# MCC8.net
KiCad netlist of a schematic drawn in EAGLE
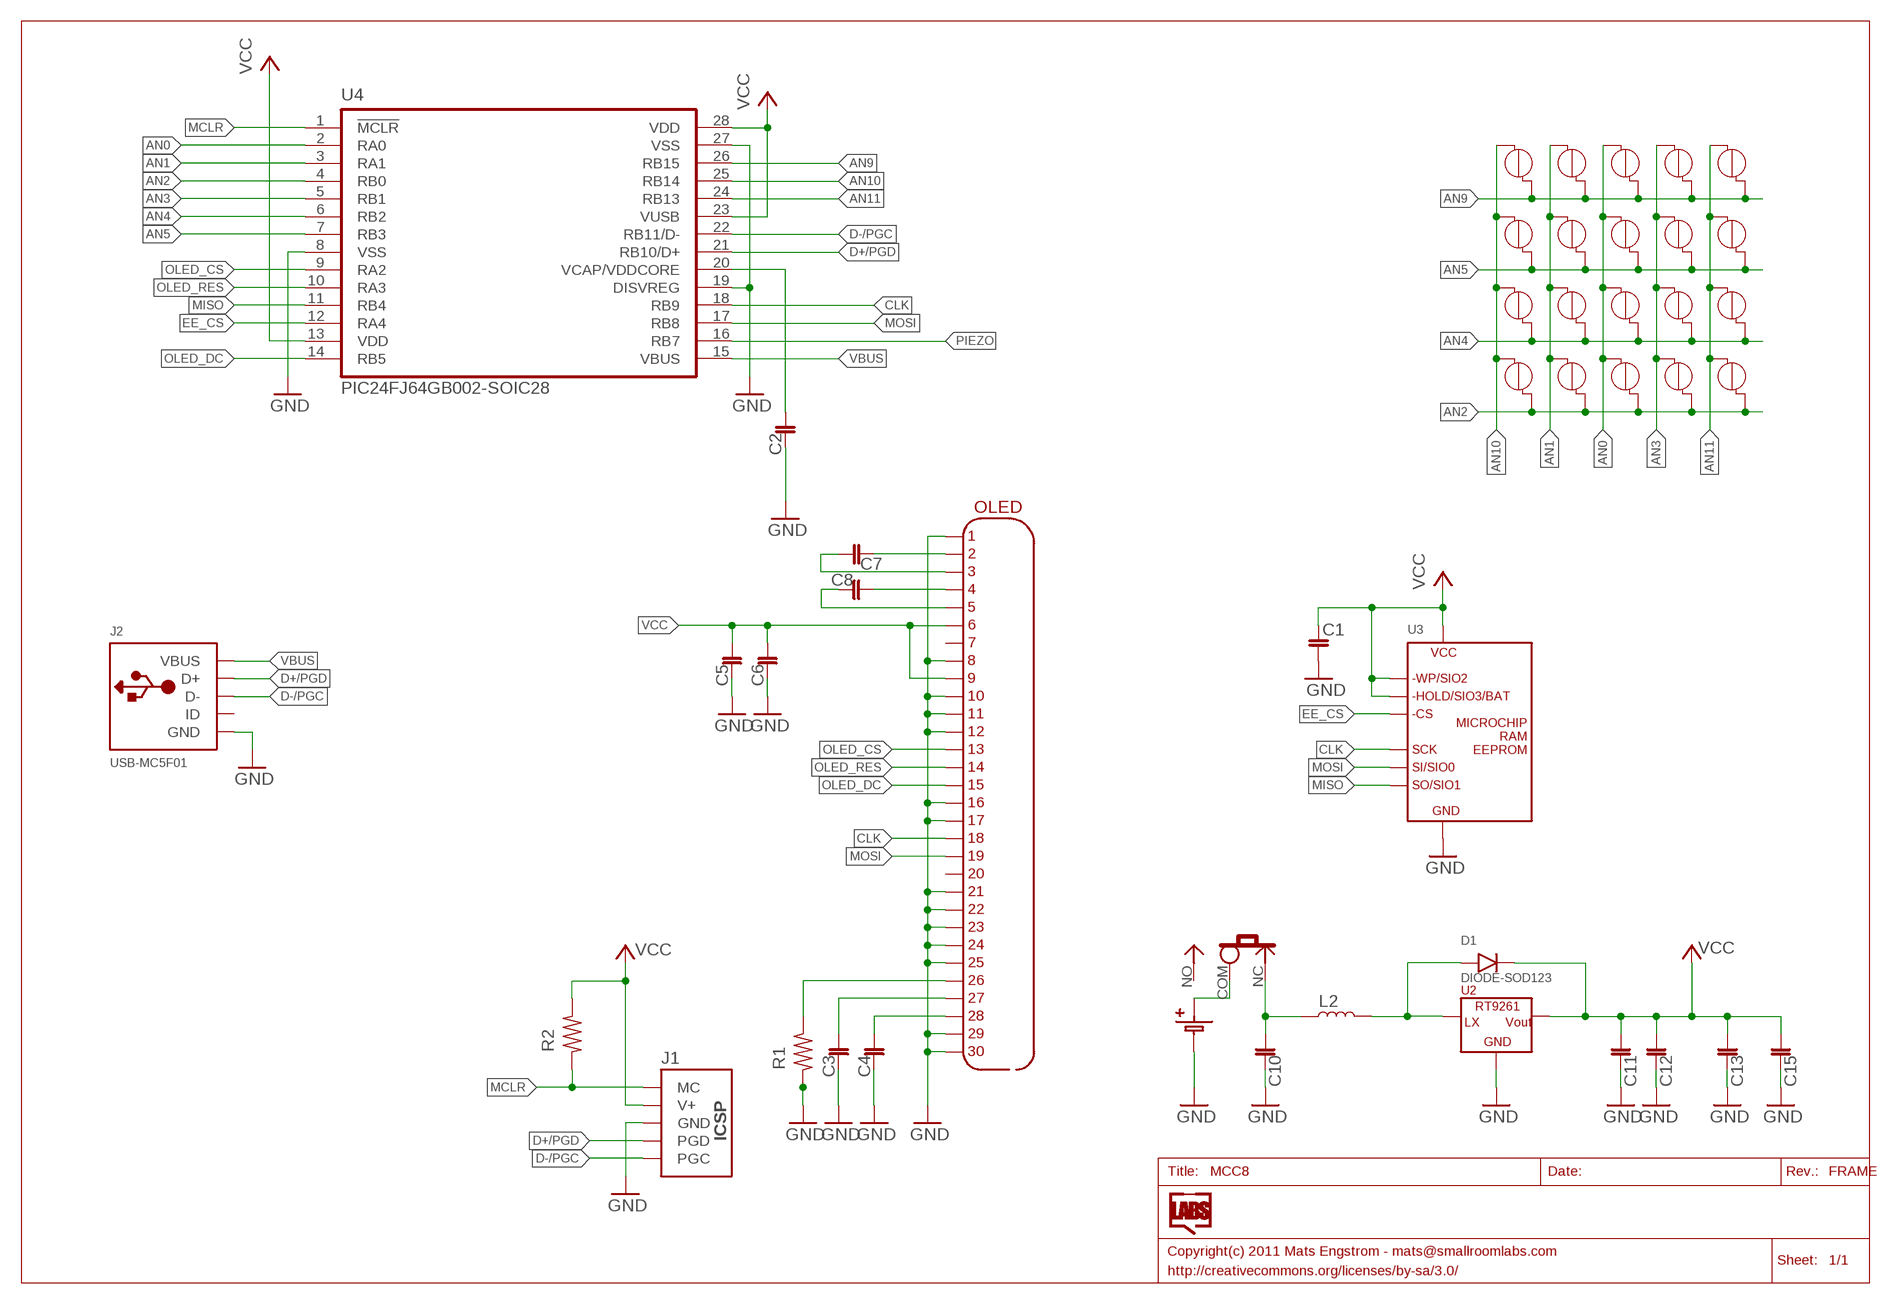
[diagram p0: schematic, sheet 1]

(export (version "E")
  (design (tool "Eeschema 10.0.6"))
  (components
    (comp (ref "B1")
      (value "TOUCH-CAP2-7")
      (footprint "eagle-import:TOUCH-CAP2-7MM")
      (libsource (lib "eagle-import") (part "TOUCH-CAP2-7"))
    )
    (comp (ref "B2")
      (value "TOUCH-CAP2-7")
      (footprint "eagle-import:TOUCH-CAP2-7MM")
      (libsource (lib "eagle-import") (part "TOUCH-CAP2-7"))
    )
    (comp (ref "B3")
      (value "TOUCH-CAP2-7")
      (footprint "eagle-import:TOUCH-CAP2-7MM")
      (libsource (lib "eagle-import") (part "TOUCH-CAP2-7"))
    )
    (comp (ref "B4")
      (value "TOUCH-CAP2-7")
      (footprint "eagle-import:TOUCH-CAP2-7MM")
      (libsource (lib "eagle-import") (part "TOUCH-CAP2-7"))
    )
    (comp (ref "B5")
      (value "TOUCH-CAP2-7")
      (footprint "eagle-import:TOUCH-CAP2-7MM")
      (libsource (lib "eagle-import") (part "TOUCH-CAP2-7"))
    )
    (comp (ref "B6")
      (value "TOUCH-CAP2-7")
      (footprint "eagle-import:TOUCH-CAP2-7MM")
      (libsource (lib "eagle-import") (part "TOUCH-CAP2-7"))
    )
    (comp (ref "B7")
      (value "TOUCH-CAP2-7")
      (footprint "eagle-import:TOUCH-CAP2-7MM")
      (libsource (lib "eagle-import") (part "TOUCH-CAP2-7"))
    )
    (comp (ref "B8")
      (value "TOUCH-CAP2-7")
      (footprint "eagle-import:TOUCH-CAP2-7MM")
      (libsource (lib "eagle-import") (part "TOUCH-CAP2-7"))
    )
    (comp (ref "B9")
      (value "TOUCH-CAP2-7")
      (footprint "eagle-import:TOUCH-CAP2-7MM")
      (libsource (lib "eagle-import") (part "TOUCH-CAP2-7"))
    )
    (comp (ref "B10")
      (value "TOUCH-CAP2-7")
      (footprint "eagle-import:TOUCH-CAP2-7MM")
      (libsource (lib "eagle-import") (part "TOUCH-CAP2-7"))
    )
    (comp (ref "B11")
      (value "TOUCH-CAP2-7")
      (footprint "eagle-import:TOUCH-CAP2-7MM")
      (libsource (lib "eagle-import") (part "TOUCH-CAP2-7"))
    )
    (comp (ref "B12")
      (value "TOUCH-CAP2-7")
      (footprint "eagle-import:TOUCH-CAP2-7MM")
      (libsource (lib "eagle-import") (part "TOUCH-CAP2-7"))
    )
    (comp (ref "B13")
      (value "TOUCH-CAP2-7")
      (footprint "eagle-import:TOUCH-CAP2-7MM")
      (libsource (lib "eagle-import") (part "TOUCH-CAP2-7"))
    )
    (comp (ref "B14")
      (value "TOUCH-CAP2-7")
      (footprint "eagle-import:TOUCH-CAP2-7MM")
      (libsource (lib "eagle-import") (part "TOUCH-CAP2-7"))
    )
    (comp (ref "B15")
      (value "TOUCH-CAP2-7")
      (footprint "eagle-import:TOUCH-CAP2-7MM")
      (libsource (lib "eagle-import") (part "TOUCH-CAP2-7"))
    )
    (comp (ref "B16")
      (value "TOUCH-CAP2-7")
      (footprint "eagle-import:TOUCH-CAP2-7MM")
      (libsource (lib "eagle-import") (part "TOUCH-CAP2-7"))
    )
    (comp (ref "B17")
      (value "TOUCH-CAP2-7")
      (footprint "eagle-import:TOUCH-CAP2-7MM")
      (libsource (lib "eagle-import") (part "TOUCH-CAP2-7"))
    )
    (comp (ref "B18")
      (value "TOUCH-CAP2-7")
      (footprint "eagle-import:TOUCH-CAP2-7MM")
      (libsource (lib "eagle-import") (part "TOUCH-CAP2-7"))
    )
    (comp (ref "B19")
      (value "TOUCH-CAP2-7")
      (footprint "eagle-import:TOUCH-CAP2-7MM")
      (libsource (lib "eagle-import") (part "TOUCH-CAP2-7"))
    )
    (comp (ref "B20")
      (value "TOUCH-CAP2-7")
      (footprint "eagle-import:TOUCH-CAP2-7MM")
      (libsource (lib "eagle-import") (part "TOUCH-CAP2-7"))
    )
    (comp (ref "BA2")
      (value "BATTERY2-AAA1")
      (footprint "eagle-import:BAT-AAA1")
      (libsource (lib "eagle-import") (part "BATTERY2-AAA1"))
    )
    (comp (ref "C1")
      (value "C-0805")
      (footprint "eagle-import:C0805")
      (libsource (lib "eagle-import") (part "C-0805"))
    )
    (comp (ref "C2")
      (value "C-0805")
      (footprint "eagle-import:C0805")
      (libsource (lib "eagle-import") (part "C-0805"))
    )
    (comp (ref "C3")
      (value "C-0805")
      (footprint "eagle-import:C0805")
      (libsource (lib "eagle-import") (part "C-0805"))
    )
    (comp (ref "C4")
      (value "C-0805")
      (footprint "eagle-import:C0805")
      (libsource (lib "eagle-import") (part "C-0805"))
    )
    (comp (ref "C5")
      (value "C-0805")
      (footprint "eagle-import:C0805")
      (libsource (lib "eagle-import") (part "C-0805"))
    )
    (comp (ref "C6")
      (value "C-0805")
      (footprint "eagle-import:C0805")
      (libsource (lib "eagle-import") (part "C-0805"))
    )
    (comp (ref "C7")
      (value "C-0805")
      (footprint "eagle-import:C0805")
      (libsource (lib "eagle-import") (part "C-0805"))
    )
    (comp (ref "C8")
      (value "C-0805")
      (footprint "eagle-import:C0805")
      (libsource (lib "eagle-import") (part "C-0805"))
    )
    (comp (ref "C10")
      (value "C-0805")
      (footprint "eagle-import:C0805")
      (libsource (lib "eagle-import") (part "C-0805"))
    )
    (comp (ref "C11")
      (value "C-0805")
      (footprint "eagle-import:C0805")
      (libsource (lib "eagle-import") (part "C-0805"))
    )
    (comp (ref "C12")
      (value "C-0805")
      (footprint "eagle-import:C0805")
      (libsource (lib "eagle-import") (part "C-0805"))
    )
    (comp (ref "C13")
      (value "C-0805")
      (footprint "eagle-import:C0805")
      (libsource (lib "eagle-import") (part "C-0805"))
    )
    (comp (ref "C15")
      (value "C-0805")
      (footprint "eagle-import:C0805")
      (libsource (lib "eagle-import") (part "C-0805"))
    )
    (comp (ref "D1")
      (value "DIODE-SOD123")
      (footprint "eagle-import:SOD123")
      (libsource (lib "eagle-import") (part "DIODE-SOD123"))
    )
    (comp (ref "J1")
      (value "ICSP-SMD-B")
      (footprint "eagle-import:ICSP-SMD-B")
      (libsource (lib "eagle-import") (part "ICSP-SMD-B"))
    )
    (comp (ref "J2")
      (value "USB-MC5F01")
      (footprint "eagle-import:USB-MICRO-MC5F01")
      (libsource (lib "eagle-import") (part "USB-MC5F01"))
    )
    (comp (ref "L2")
      (value "L-BOURNS-SRP7030")
      (footprint "eagle-import:IND-BOURNS-SRP7030")
      (libsource (lib "eagle-import") (part "L-BOURNS-SRP7030"))
    )
    (comp (ref "R1")
      (value "R-0805")
      (footprint "eagle-import:R0805")
      (libsource (lib "eagle-import") (part "R-0805"))
    )
    (comp (ref "R2")
      (value "R-0805")
      (footprint "eagle-import:R0805")
      (libsource (lib "eagle-import") (part "R-0805"))
    )
    (comp (ref "SW1")
      (value "SLIDE1-PCM12")
      (footprint "eagle-import:SW-PCM12")
      (libsource (lib "eagle-import") (part "SLIDE1-PCM12"))
    )
    (comp (ref "U$2")
      (value "OLED30-A")
      (footprint "eagle-import:OLED128X64")
      (libsource (lib "eagle-import") (part "OLED30-A"))
    )
    (comp (ref "U2")
      (value "RT9261-SOT89")
      (footprint "eagle-import:SOT89")
      (libsource (lib "eagle-import") (part "RT9261-SOT89"))
    )
    (comp (ref "U3")
      (value "MICROCHIP-SERIALMEM8")
      (footprint "eagle-import:SO08")
      (libsource (lib "eagle-import") (part "MICROCHIP-SERIALMEM8"))
    )
    (comp (ref "U4")
      (value "PIC24FJ64GB002-SOIC28")
      (footprint "eagle-import:SO28W")
      (libsource (lib "eagle-import") (part "PIC24FJ64GB002-SOIC28"))
    )
  )
  (nets
    (net (code "1") (name "AN0") (class "Default")
      (node (ref "B10") (pin "P$1") (pinfunction "P$1_P$1") (pintype "bidirectional"))
      (node (ref "B11") (pin "P$1") (pinfunction "P$1_P$1") (pintype "bidirectional"))
      (node (ref "B12") (pin "P$1") (pinfunction "P$1_P$1") (pintype "bidirectional"))
      (node (ref "B9") (pin "P$1") (pinfunction "P$1_P$1") (pintype "bidirectional"))
      (node (ref "U4") (pin "2") (pinfunction "RA0_2") (pintype "bidirectional"))
    )
    (net (code "2") (name "AN1") (class "Default")
      (node (ref "B5") (pin "P$1") (pinfunction "P$1_P$1") (pintype "bidirectional"))
      (node (ref "B6") (pin "P$1") (pinfunction "P$1_P$1") (pintype "bidirectional"))
      (node (ref "B7") (pin "P$1") (pinfunction "P$1_P$1") (pintype "bidirectional"))
      (node (ref "B8") (pin "P$1") (pinfunction "P$1_P$1") (pintype "bidirectional"))
      (node (ref "U4") (pin "3") (pinfunction "RA1_3") (pintype "bidirectional"))
    )
    (net (code "3") (name "AN2") (class "Default")
      (node (ref "B12") (pin "P$2") (pinfunction "P$2_P$2") (pintype "bidirectional"))
      (node (ref "B16") (pin "P$2") (pinfunction "P$2_P$2") (pintype "bidirectional"))
      (node (ref "B20") (pin "P$2") (pinfunction "P$2_P$2") (pintype "bidirectional"))
      (node (ref "B4") (pin "P$2") (pinfunction "P$2_P$2") (pintype "bidirectional"))
      (node (ref "B8") (pin "P$2") (pinfunction "P$2_P$2") (pintype "bidirectional"))
      (node (ref "U4") (pin "4") (pinfunction "RB0_4") (pintype "bidirectional"))
    )
    (net (code "4") (name "AN3") (class "Default")
      (node (ref "B13") (pin "P$1") (pinfunction "P$1_P$1") (pintype "bidirectional"))
      (node (ref "B14") (pin "P$1") (pinfunction "P$1_P$1") (pintype "bidirectional"))
      (node (ref "B15") (pin "P$1") (pinfunction "P$1_P$1") (pintype "bidirectional"))
      (node (ref "B16") (pin "P$1") (pinfunction "P$1_P$1") (pintype "bidirectional"))
      (node (ref "U4") (pin "5") (pinfunction "RB1_5") (pintype "bidirectional"))
    )
    (net (code "5") (name "AN4") (class "Default")
      (node (ref "B11") (pin "P$2") (pinfunction "P$2_P$2") (pintype "bidirectional"))
      (node (ref "B15") (pin "P$2") (pinfunction "P$2_P$2") (pintype "bidirectional"))
      (node (ref "B19") (pin "P$2") (pinfunction "P$2_P$2") (pintype "bidirectional"))
      (node (ref "B3") (pin "P$2") (pinfunction "P$2_P$2") (pintype "bidirectional"))
      (node (ref "B7") (pin "P$2") (pinfunction "P$2_P$2") (pintype "bidirectional"))
      (node (ref "U4") (pin "6") (pinfunction "RB2_6") (pintype "bidirectional"))
    )
    (net (code "6") (name "AN5") (class "Default")
      (node (ref "B10") (pin "P$2") (pinfunction "P$2_P$2") (pintype "bidirectional"))
      (node (ref "B14") (pin "P$2") (pinfunction "P$2_P$2") (pintype "bidirectional"))
      (node (ref "B18") (pin "P$2") (pinfunction "P$2_P$2") (pintype "bidirectional"))
      (node (ref "B2") (pin "P$2") (pinfunction "P$2_P$2") (pintype "bidirectional"))
      (node (ref "B6") (pin "P$2") (pinfunction "P$2_P$2") (pintype "bidirectional"))
      (node (ref "U4") (pin "7") (pinfunction "RB3_7") (pintype "bidirectional"))
    )
    (net (code "7") (name "AN9") (class "Default")
      (node (ref "B1") (pin "P$2") (pinfunction "P$2_P$2") (pintype "bidirectional"))
      (node (ref "B13") (pin "P$2") (pinfunction "P$2_P$2") (pintype "bidirectional"))
      (node (ref "B17") (pin "P$2") (pinfunction "P$2_P$2") (pintype "bidirectional"))
      (node (ref "B5") (pin "P$2") (pinfunction "P$2_P$2") (pintype "bidirectional"))
      (node (ref "B9") (pin "P$2") (pinfunction "P$2_P$2") (pintype "bidirectional"))
      (node (ref "U4") (pin "26") (pinfunction "RB15_26") (pintype "bidirectional"))
    )
    (net (code "8") (name "AN10") (class "Default")
      (node (ref "B1") (pin "P$1") (pinfunction "P$1_P$1") (pintype "bidirectional"))
      (node (ref "B2") (pin "P$1") (pinfunction "P$1_P$1") (pintype "bidirectional"))
      (node (ref "B3") (pin "P$1") (pinfunction "P$1_P$1") (pintype "bidirectional"))
      (node (ref "B4") (pin "P$1") (pinfunction "P$1_P$1") (pintype "bidirectional"))
      (node (ref "U4") (pin "25") (pinfunction "RB14_25") (pintype "bidirectional"))
    )
    (net (code "9") (name "AN11") (class "Default")
      (node (ref "B17") (pin "P$1") (pinfunction "P$1_P$1") (pintype "bidirectional"))
      (node (ref "B18") (pin "P$1") (pinfunction "P$1_P$1") (pintype "bidirectional"))
      (node (ref "B19") (pin "P$1") (pinfunction "P$1_P$1") (pintype "bidirectional"))
      (node (ref "B20") (pin "P$1") (pinfunction "P$1_P$1") (pintype "bidirectional"))
      (node (ref "U4") (pin "24") (pinfunction "RB13_24") (pintype "bidirectional"))
    )
    (net (code "10") (name "CLK") (class "Default")
      (node (ref "U$2") (pin "P$18") (pinfunction "P$18_P$18") (pintype "bidirectional"))
      (node (ref "U3") (pin "6") (pinfunction "SCK_6") (pintype "bidirectional"))
      (node (ref "U4") (pin "18") (pinfunction "RB9_18") (pintype "bidirectional"))
    )
    (net (code "11") (name "D+{slash}PGD") (class "Default")
      (node (ref "J1") (pin "PGD") (pinfunction "PGD_PGD") (pintype "output"))
      (node (ref "J2") (pin "P3") (pinfunction "D+_P3") (pintype "bidirectional"))
      (node (ref "U4") (pin "21") (pinfunction "RB10/D+_21") (pintype "bidirectional"))
    )
    (net (code "12") (name "D-{slash}PGC") (class "Default")
      (node (ref "J1") (pin "PGC") (pinfunction "PGC_PGC") (pintype "output"))
      (node (ref "J2") (pin "P2") (pinfunction "D-_P2") (pintype "bidirectional"))
      (node (ref "U4") (pin "22") (pinfunction "RB11/D-_22") (pintype "bidirectional"))
    )
    (net (code "13") (name "EE_CS") (class "Default")
      (node (ref "U3") (pin "1") (pinfunction "CS_1") (pintype "bidirectional"))
      (node (ref "U4") (pin "12") (pinfunction "RA4_12") (pintype "bidirectional"))
    )
    (net (code "14") (name "GND") (class "Default")
      (node (ref "BA2") (pin "MINUS") (pinfunction "NEG_MINUS") (pintype "power_in"))
      (node (ref "C1") (pin "2") (pinfunction "P$2_2") (pintype "bidirectional"))
      (node (ref "C10") (pin "2") (pinfunction "P$2_2") (pintype "bidirectional"))
      (node (ref "C11") (pin "2") (pinfunction "P$2_2") (pintype "bidirectional"))
      (node (ref "C12") (pin "2") (pinfunction "P$2_2") (pintype "bidirectional"))
      (node (ref "C13") (pin "2") (pinfunction "P$2_2") (pintype "bidirectional"))
      (node (ref "C15") (pin "2") (pinfunction "P$2_2") (pintype "bidirectional"))
      (node (ref "C2") (pin "2") (pinfunction "P$2_2") (pintype "bidirectional"))
      (node (ref "C3") (pin "2") (pinfunction "P$2_2") (pintype "bidirectional"))
      (node (ref "C4") (pin "2") (pinfunction "P$2_2") (pintype "bidirectional"))
      (node (ref "C5") (pin "2") (pinfunction "P$2_2") (pintype "bidirectional"))
      (node (ref "C6") (pin "2") (pinfunction "P$2_2") (pintype "bidirectional"))
      (node (ref "J1") (pin "GND") (pinfunction "GND_GND") (pintype "power_in"))
      (node (ref "J2") (pin "P5") (pinfunction "GND_P5") (pintype "power_in"))
      (node (ref "R1") (pin "1") (pinfunction "P$1_1") (pintype "bidirectional"))
      (node (ref "U$2") (pin "P$1") (pinfunction "P$1_P$1") (pintype "bidirectional"))
      (node (ref "U$2") (pin "P$10") (pinfunction "P$10_P$10") (pintype "bidirectional"))
      (node (ref "U$2") (pin "P$11") (pinfunction "P$11_P$11") (pintype "bidirectional"))
      (node (ref "U$2") (pin "P$12") (pinfunction "P$12_P$12") (pintype "bidirectional"))
      (node (ref "U$2") (pin "P$16") (pinfunction "P$16_P$16") (pintype "bidirectional"))
      (node (ref "U$2") (pin "P$17") (pinfunction "P$17_P$17") (pintype "bidirectional"))
      (node (ref "U$2") (pin "P$21") (pinfunction "P$21_P$21") (pintype "bidirectional"))
      (node (ref "U$2") (pin "P$22") (pinfunction "P$22_P$22") (pintype "bidirectional"))
      (node (ref "U$2") (pin "P$23") (pinfunction "P$23_P$23") (pintype "bidirectional"))
      (node (ref "U$2") (pin "P$24") (pinfunction "P$24_P$24") (pintype "bidirectional"))
      (node (ref "U$2") (pin "P$25") (pinfunction "P$25_P$25") (pintype "bidirectional"))
      (node (ref "U$2") (pin "P$29") (pinfunction "P$29_P$29") (pintype "bidirectional"))
      (node (ref "U$2") (pin "P$30") (pinfunction "P$30_P$30") (pintype "bidirectional"))
      (node (ref "U$2") (pin "P$8") (pinfunction "P$8_P$8") (pintype "bidirectional"))
      (node (ref "U2") (pin "1") (pinfunction "GND_1") (pintype "power_in"))
      (node (ref "U3") (pin "4") (pinfunction "GROUND_4") (pintype "power_in"))
      (node (ref "U4") (pin "19") (pinfunction "DISVREG_19") (pintype "passive"))
      (node (ref "U4") (pin "27") (pinfunction "VSS_27") (pintype "power_in"))
      (node (ref "U4") (pin "8") (pinfunction "VSS_8") (pintype "power_in"))
    )
    (net (code "15") (name "MCLR") (class "Default")
      (node (ref "J1") (pin "VPP") (pinfunction "MC_VPP") (pintype "output"))
      (node (ref "R2") (pin "1") (pinfunction "P$1_1") (pintype "bidirectional"))
      (node (ref "U4") (pin "1") (pinfunction "~{MCLR}_1") (pintype "bidirectional"))
    )
    (net (code "16") (name "MISO") (class "Default")
      (node (ref "U3") (pin "2") (pinfunction "SO_2") (pintype "bidirectional"))
      (node (ref "U4") (pin "11") (pinfunction "RB4_11") (pintype "bidirectional"))
    )
    (net (code "17") (name "MOSI") (class "Default")
      (node (ref "U$2") (pin "P$19") (pinfunction "P$19_P$19") (pintype "bidirectional"))
      (node (ref "U3") (pin "5") (pinfunction "SI_5") (pintype "bidirectional"))
      (node (ref "U4") (pin "17") (pinfunction "RB8_17") (pintype "bidirectional"))
    )
    (net (code "18") (name "Net-(BA2-POS1)") (class "Default")
      (node (ref "BA2") (pin "PLUS") (pinfunction "POS1_PLUS") (pintype "power_in"))
      (node (ref "SW1") (pin "COM") (pinfunction "COM_COM") (pintype "bidirectional"))
    )
    (net (code "19") (name "Net-(C2-P$1)") (class "Default")
      (node (ref "C2") (pin "1") (pinfunction "P$1_1") (pintype "bidirectional"))
      (node (ref "U4") (pin "20") (pinfunction "VCAP/VDDCORE_20") (pintype "power_in"))
    )
    (net (code "20") (name "Net-(C3-P$1)") (class "Default")
      (node (ref "C3") (pin "1") (pinfunction "P$1_1") (pintype "bidirectional"))
      (node (ref "U$2") (pin "P$27") (pinfunction "P$27_P$27") (pintype "bidirectional"))
    )
    (net (code "21") (name "Net-(C4-P$1)") (class "Default")
      (node (ref "C4") (pin "1") (pinfunction "P$1_1") (pintype "bidirectional"))
      (node (ref "U$2") (pin "P$28") (pinfunction "P$28_P$28") (pintype "bidirectional"))
    )
    (net (code "22") (name "Net-(C7-P$1)") (class "Default")
      (node (ref "C7") (pin "1") (pinfunction "P$1_1") (pintype "bidirectional"))
      (node (ref "U$2") (pin "P$3") (pinfunction "P$3_P$3") (pintype "bidirectional"))
    )
    (net (code "23") (name "Net-(C7-P$2)") (class "Default")
      (node (ref "C7") (pin "2") (pinfunction "P$2_2") (pintype "bidirectional"))
      (node (ref "U$2") (pin "P$2") (pinfunction "P$2_P$2") (pintype "bidirectional"))
    )
    (net (code "24") (name "Net-(C8-P$1)") (class "Default")
      (node (ref "C8") (pin "1") (pinfunction "P$1_1") (pintype "bidirectional"))
      (node (ref "U$2") (pin "P$4") (pinfunction "P$4_P$4") (pintype "bidirectional"))
    )
    (net (code "25") (name "Net-(C8-P$2)") (class "Default")
      (node (ref "C8") (pin "2") (pinfunction "P$2_2") (pintype "bidirectional"))
      (node (ref "U$2") (pin "P$5") (pinfunction "P$5_P$5") (pintype "bidirectional"))
    )
    (net (code "26") (name "Net-(C10-P$1)") (class "Default")
      (node (ref "C10") (pin "1") (pinfunction "P$1_1") (pintype "bidirectional"))
      (node (ref "L2") (pin "P$1") (pinfunction "P$1_P$1") (pintype "bidirectional"))
      (node (ref "SW1") (pin "NC") (pinfunction "NC_NC") (pintype "bidirectional"))
    )
    (net (code "27") (name "Net-(R1-P$2)") (class "Default")
      (node (ref "R1") (pin "2") (pinfunction "P$2_2") (pintype "bidirectional"))
      (node (ref "U$2") (pin "P$26") (pinfunction "P$26_P$26") (pintype "bidirectional"))
    )
    (net (code "28") (name "Net-(U2-LX)") (class "Default")
      (node (ref "D1") (pin "A") (pinfunction "A_A") (pintype "passive"))
      (node (ref "L2") (pin "P$2") (pinfunction "P$2_P$2") (pintype "bidirectional"))
      (node (ref "U2") (pin "3") (pinfunction "LX_3") (pintype "bidirectional"))
    )
    (net (code "29") (name "OLED_CS") (class "Default")
      (node (ref "U$2") (pin "P$13") (pinfunction "P$13_P$13") (pintype "bidirectional"))
      (node (ref "U4") (pin "9") (pinfunction "RA2_9") (pintype "bidirectional"))
    )
    (net (code "30") (name "OLED_DC") (class "Default")
      (node (ref "U$2") (pin "P$15") (pinfunction "P$15_P$15") (pintype "bidirectional"))
      (node (ref "U4") (pin "14") (pinfunction "RB5_14") (pintype "bidirectional"))
    )
    (net (code "31") (name "OLED_RES") (class "Default")
      (node (ref "U$2") (pin "P$14") (pinfunction "P$14_P$14") (pintype "bidirectional"))
      (node (ref "U4") (pin "10") (pinfunction "RA3_10") (pintype "bidirectional"))
    )
    (net (code "32") (name "PIEZO") (class "Default")
      (node (ref "U4") (pin "16") (pinfunction "RB7_16") (pintype "bidirectional"))
    )
    (net (code "33") (name "VBUS") (class "Default")
      (node (ref "J2") (pin "P1") (pinfunction "VBUS_P1") (pintype "power_in"))
      (node (ref "U4") (pin "15") (pinfunction "VBUS_15") (pintype "power_in"))
    )
    (net (code "34") (name "VCC") (class "Default")
      (node (ref "C1") (pin "1") (pinfunction "P$1_1") (pintype "bidirectional"))
      (node (ref "C11") (pin "1") (pinfunction "P$1_1") (pintype "bidirectional"))
      (node (ref "C12") (pin "1") (pinfunction "P$1_1") (pintype "bidirectional"))
      (node (ref "C13") (pin "1") (pinfunction "P$1_1") (pintype "bidirectional"))
      (node (ref "C15") (pin "1") (pinfunction "P$1_1") (pintype "bidirectional"))
      (node (ref "C5") (pin "1") (pinfunction "P$1_1") (pintype "bidirectional"))
      (node (ref "C6") (pin "1") (pinfunction "P$1_1") (pintype "bidirectional"))
      (node (ref "D1") (pin "C") (pinfunction "C_C") (pintype "passive"))
      (node (ref "J1") (pin "V+") (pinfunction "V+_V+") (pintype "power_in"))
      (node (ref "R2") (pin "2") (pinfunction "P$2_2") (pintype "bidirectional"))
      (node (ref "U$2") (pin "P$6") (pinfunction "P$6_P$6") (pintype "bidirectional"))
      (node (ref "U$2") (pin "P$9") (pinfunction "P$9_P$9") (pintype "bidirectional"))
      (node (ref "U2") (pin "2") (pinfunction "VOUT_2") (pintype "bidirectional"))
      (node (ref "U2") (pin "2@1") (pinfunction "VOUT_2@1") (pintype "bidirectional"))
      (node (ref "U3") (pin "3") (pinfunction "WP_3") (pintype "bidirectional"))
      (node (ref "U3") (pin "7") (pinfunction "HOLD_7") (pintype "bidirectional"))
      (node (ref "U3") (pin "8") (pinfunction "POW_8") (pintype "power_in"))
      (node (ref "U4") (pin "13") (pinfunction "VDD_13") (pintype "power_in"))
      (node (ref "U4") (pin "23") (pinfunction "VUSB_23") (pintype "bidirectional"))
      (node (ref "U4") (pin "28") (pinfunction "VDD_28") (pintype "power_in"))
    )
    (net (code "35") (name "unconnected-(J2-ID-PadP4)") (class "Default")
      (node (ref "J2") (pin "P4") (pinfunction "ID_P4") (pintype "bidirectional"))
    )
    (net (code "36") (name "unconnected-(SW1-PadNO)") (class "Default")
      (node (ref "SW1") (pin "NO") (pinfunction "NO_NO") (pintype "bidirectional"))
    )
    (net (code "37") (name "unconnected-(U$2-PadP$7)") (class "Default")
      (node (ref "U$2") (pin "P$7") (pinfunction "P$7_P$7") (pintype "bidirectional"))
    )
    (net (code "38") (name "unconnected-(U$2-PadP$20)") (class "Default")
      (node (ref "U$2") (pin "P$20") (pinfunction "P$20_P$20") (pintype "bidirectional"))
    )
  )
)
